# Magileff_NADKONVEER.net
KiCad netlist of a schematic drawn in EAGLE
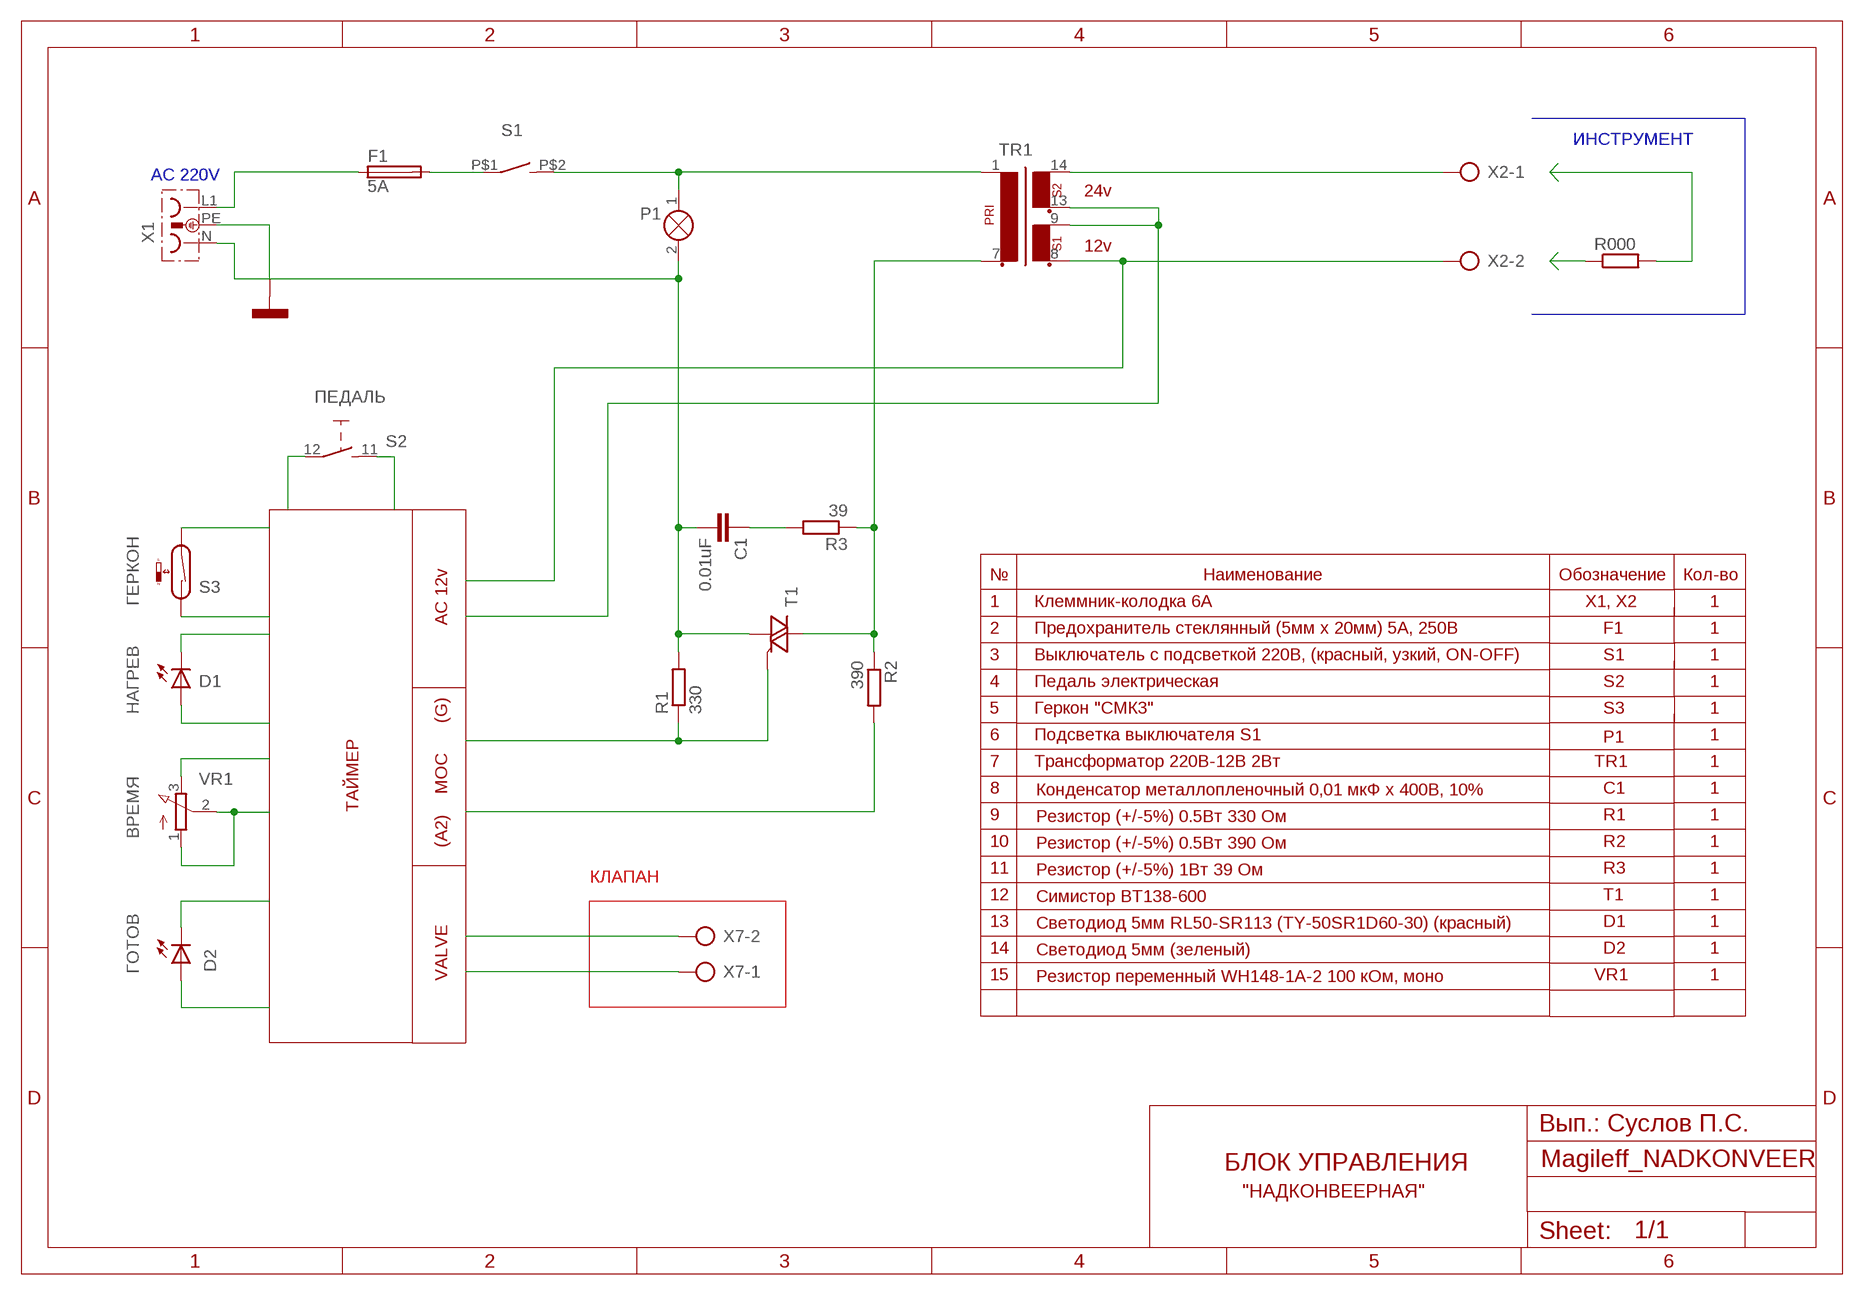
[diagram p0: schematic, sheet 1]

(export (version "E")
  (design (tool "Eeschema 10.0.6"))
  (components
    (comp (ref "C1")
      (value "0.01uF")
      (footprint "eagle-import:C025-030X050")
      (libsource (lib "eagle-import") (part "C-EU025-030X050"))
    )
    (comp (ref "F1")
      (value "5A")
      (footprint "eagle-import:GSH15")
      (fields (field (name "MPN") "64900001039"))
      (libsource (lib "eagle-import") (part "GSH15"))
    )
    (comp (ref "GG")
      (value "MASSE_ALLGEMEIN")
      (footprint "eagle-import:MASSE_ALLGEMEIN")
      (libsource (lib "eagle-import") (part "MASSE_ALLGEMEIN"))
    )
    (comp (ref "P1")
      (value "SIGNALLAMPE")
      (footprint "eagle-import:LAMPE")
      (libsource (lib "eagle-import") (part "SIGNALLAMPE"))
    )
    (comp (ref "R000")
      (value "R-EU_R0201")
      (footprint "eagle-import:R0201")
      (libsource (lib "eagle-import") (part "R-EU_R0201"))
    )
    (comp (ref "R1")
      (value "330")
      (footprint "eagle-import:0207_5V")
      (libsource (lib "eagle-import") (part "R-EU_0207/5V"))
    )
    (comp (ref "R2")
      (value "390")
      (footprint "eagle-import:0207_5V")
      (libsource (lib "eagle-import") (part "R-EU_0207/5V"))
    )
    (comp (ref "R3")
      (value "39")
      (footprint "eagle-import:0207_5V")
      (libsource (lib "eagle-import") (part "R-EU_0207/5V"))
    )
    (comp (ref "S1")
      (value "SCHLIESSER_ARBEITSKONTAKT")
      (footprint "eagle-import:1")
      (libsource (lib "eagle-import") (part "SCHLIESSER_ARBEITSKONTAKT"))
    )
    (comp (ref "S2")
      (value "ПЕДАЛЬ")
      (footprint "eagle-import:KIPPSCHALTER_AUS")
      (libsource (lib "eagle-import") (part "SCHALTER_SCHLIESSER_HANDBETAETIGT"))
    )
    (comp (ref "S3")
      (value "ГЕРКОН")
      (footprint "eagle-import:CT10-G1")
      (fields (field (name "MF") "COTO TECHNOLOGY") (field (name "MPN") "CT10-1530-G1"))
      (libsource (lib "eagle-import") (part "REED-SWITCH-CT10-1530-G1"))
    )
    (comp (ref "T1")
      (value "BTA26-V")
      (footprint "eagle-import:TOP3S-1")
      (libsource (lib "eagle-import") (part "BTA26-V"))
    )
    (comp (ref "TR1")
      (value "EI54-2B")
      (footprint "eagle-import:EI54-2B")
      (libsource (lib "eagle-import") (part "EI54-2B"))
    )
    (comp (ref "X1")
      (value "STECKDOSE")
      (footprint "eagle-import:STECKDOSE")
      (libsource (lib "eagle-import") (part "STECKDOSE"))
    )
    (comp (ref "X2")
      (value "AK500/2")
      (footprint "eagle-import:AK500_2")
      (libsource (lib "eagle-import") (part "AK500/2"))
    )
    (comp (ref "X7")
      (value "AK500/2")
      (footprint "eagle-import:AK500_2")
      (libsource (lib "eagle-import") (part "AK500/2"))
    )
    (comp (ref "ВРЕМЯ")
      (value "3RP/1610N")
      (footprint "eagle-import:3RP_1610N")
      (libsource (lib "eagle-import") (part "3RP/1610N"))
    )
    (comp (ref "ГОТОВ")
      (value "НАГРЕВ")
      (footprint "eagle-import:LED5MM")
      (libsource (lib "eagle-import") (part "LED5MM"))
    )
    (comp (ref "ГОТОВ1")
      (value "ГОТОВ")
      (footprint "eagle-import:LED5MM")
      (libsource (lib "eagle-import") (part "LED5MM"))
    )
  )
  (nets
    (net (code "1") (name "Net-(C1-Pad1)") (class "Default")
      (node (ref "C1") (pin "1") (pinfunction "1_1") (pintype "passive"))
      (node (ref "R3") (pin "2") (pinfunction "2_2") (pintype "passive"))
    )
    (net (code "2") (name "Net-(F1-Pad1)") (class "Default")
      (node (ref "F1") (pin "1") (pinfunction "1_1") (pintype "passive"))
      (node (ref "X1") (pin "L1") (pinfunction "L1_L1") (pintype "passive"))
    )
    (net (code "3") (name "Net-(GG-0V)") (class "Default")
      (node (ref "GG") (pin "1") (pinfunction "0V_1") (pintype "passive"))
      (node (ref "X1") (pin "PE") (pinfunction "PE_PE") (pintype "passive"))
    )
    (net (code "4") (name "Net-(P1-X1)") (class "Default")
      (node (ref "P1") (pin "1") (pinfunction "X1_1") (pintype "passive"))
      (node (ref "S1") (pin "P$2") (pinfunction "3_P$2") (pintype "passive"))
      (node (ref "TR1") (pin "1") (pinfunction "1_1") (pintype "passive"))
    )
    (net (code "5") (name "Net-(P1-X2)") (class "Default")
      (node (ref "C1") (pin "2") (pinfunction "2_2") (pintype "passive"))
      (node (ref "P1") (pin "2") (pinfunction "X2_2") (pintype "passive"))
      (node (ref "R1") (pin "2") (pinfunction "2_2") (pintype "passive"))
      (node (ref "T1") (pin "A1") (pinfunction "A1_A1") (pintype "passive"))
      (node (ref "X1") (pin "N") (pinfunction "N_N") (pintype "passive"))
    )
    (net (code "6") (name "Net-(R1-Pad1)") (class "Default")
      (node (ref "R1") (pin "1") (pinfunction "1_1") (pintype "passive"))
      (node (ref "T1") (pin "G") (pinfunction "G_G") (pintype "passive"))
    )
    (net (code "7") (name "Net-(S1-4)") (class "Default")
      (node (ref "F1") (pin "2") (pinfunction "2_2") (pintype "passive"))
      (node (ref "S1") (pin "P$1") (pinfunction "4_P$1") (pintype "passive"))
    )
    (net (code "8") (name "Net-(TR1-2)") (class "Default")
      (node (ref "R2") (pin "1") (pinfunction "1_1") (pintype "passive"))
      (node (ref "R3") (pin "1") (pinfunction "1_1") (pintype "passive"))
      (node (ref "T1") (pin "A2") (pinfunction "A2_A2") (pintype "passive"))
      (node (ref "TR1") (pin "7") (pinfunction "2_7") (pintype "passive"))
    )
    (net (code "9") (name "Net-(TR1-3)") (class "Default")
      (node (ref "TR1") (pin "8") (pinfunction "3_8") (pintype "passive"))
      (node (ref "X2") (pin "2") (pinfunction "KL_2") (pintype "passive"))
    )
    (net (code "10") (name "Net-(TR1-4)") (class "Default")
      (node (ref "TR1") (pin "13") (pinfunction "5_13") (pintype "passive"))
      (node (ref "TR1") (pin "9") (pinfunction "4_9") (pintype "passive"))
    )
    (net (code "11") (name "Net-(TR1-6)") (class "Default")
      (node (ref "TR1") (pin "14") (pinfunction "6_14") (pintype "passive"))
      (node (ref "X2") (pin "1") (pinfunction "KL_1") (pintype "passive"))
    )
    (net (code "12") (name "Net-(ВРЕМЯ-A)") (class "Default")
      (node (ref "ВРЕМЯ") (pin "1") (pinfunction "A_1") (pintype "passive"))
      (node (ref "ВРЕМЯ") (pin "2") (pinfunction "S_2") (pintype "passive"))
    )
    (net (code "13") (name "unconnected-(R000-Pad1)") (class "Default")
      (node (ref "R000") (pin "1") (pinfunction "1_1") (pintype "passive"))
    )
    (net (code "14") (name "unconnected-(R000-Pad2)") (class "Default")
      (node (ref "R000") (pin "2") (pinfunction "2_2") (pintype "passive"))
    )
    (net (code "15") (name "unconnected-(R2-Pad2)") (class "Default")
      (node (ref "R2") (pin "2") (pinfunction "2_2") (pintype "passive"))
    )
    (net (code "16") (name "unconnected-(S2-CS1-Pad11)") (class "Default")
      (node (ref "S2") (pin "11") (pinfunction "CS1_11") (pintype "passive"))
    )
    (net (code "17") (name "unconnected-(S2-S1-Pad12)") (class "Default")
      (node (ref "S2") (pin "12") (pinfunction "S1_12") (pintype "passive"))
    )
    (net (code "18") (name "unconnected-(S3-Pad1)") (class "Default")
      (node (ref "S3") (pin "1") (pinfunction "1_1") (pintype "passive"))
    )
    (net (code "19") (name "unconnected-(S3-Pad2)") (class "Default")
      (node (ref "S3") (pin "2") (pinfunction "2_2") (pintype "passive"))
    )
    (net (code "20") (name "unconnected-(X7A-KL-Pad1)") (class "Default")
      (node (ref "X7") (pin "1") (pinfunction "KL_1") (pintype "passive"))
    )
    (net (code "21") (name "unconnected-(X7B-KL-Pad2)") (class "Default")
      (node (ref "X7") (pin "2") (pinfunction "KL_2") (pintype "passive"))
    )
    (net (code "22") (name "unconnected-(ВРЕМЯ-E-Pad3)") (class "Default")
      (node (ref "ВРЕМЯ") (pin "3") (pinfunction "E_3") (pintype "passive"))
    )
    (net (code "23") (name "unconnected-(ГОТОВ-C-PadK)") (class "Default")
      (node (ref "ГОТОВ") (pin "K") (pinfunction "C_K") (pintype "passive"))
    )
    (net (code "24") (name "unconnected-(ГОТОВ-PadA)") (class "Default")
      (node (ref "ГОТОВ") (pin "A") (pinfunction "A_A") (pintype "passive"))
    )
    (net (code "25") (name "unconnected-(ГОТОВ1-C-PadK)") (class "Default")
      (node (ref "ГОТОВ1") (pin "K") (pinfunction "C_K") (pintype "passive"))
    )
    (net (code "26") (name "unconnected-(ГОТОВ1-PadA)") (class "Default")
      (node (ref "ГОТОВ1") (pin "A") (pinfunction "A_A") (pintype "passive"))
    )
  )
)
